# tube-connector.net
KiCad netlist of a schematic drawn in EAGLE
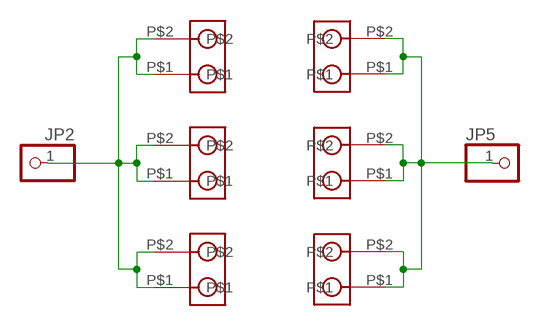
[diagram p0: schematic, sheet 1]

(export (version "E")
  (design (tool "Eeschema 10.0.6"))
  (components
    (comp (ref "JP2")
      (value "PINHD-1X1")
      (footprint "eagle-import:1X01")
      (libsource (lib "eagle-import") (part "PINHD-1X1"))
    )
    (comp (ref "JP5")
      (value "PINHD-1X1")
      (footprint "eagle-import:1X01")
      (libsource (lib "eagle-import") (part "PINHD-1X1"))
    )
    (comp (ref "U$1")
      (value "GM-CONNECTOR")
      (footprint "eagle-import:GM-CONNECTOR")
      (libsource (lib "eagle-import") (part "GM-CONNECTOR"))
    )
    (comp (ref "U$2")
      (value "GM-CONNECTOR")
      (footprint "eagle-import:GM-CONNECTOR")
      (libsource (lib "eagle-import") (part "GM-CONNECTOR"))
    )
    (comp (ref "U$3")
      (value "GM-CONNECTOR")
      (footprint "eagle-import:GM-CONNECTOR")
      (libsource (lib "eagle-import") (part "GM-CONNECTOR"))
    )
    (comp (ref "U$4")
      (value "GM-CONNECTOR")
      (footprint "eagle-import:GM-CONNECTOR")
      (libsource (lib "eagle-import") (part "GM-CONNECTOR"))
    )
    (comp (ref "U$5")
      (value "GM-CONNECTOR")
      (footprint "eagle-import:GM-CONNECTOR")
      (libsource (lib "eagle-import") (part "GM-CONNECTOR"))
    )
    (comp (ref "U$6")
      (value "GM-CONNECTOR")
      (footprint "eagle-import:GM-CONNECTOR")
      (libsource (lib "eagle-import") (part "GM-CONNECTOR"))
    )
  )
  (nets
    (net (code "1") (name "Net-(JP2-Pad1)") (class "Default")
      (node (ref "JP2") (pin "1") (pinfunction "1_1") (pintype "passive"))
      (node (ref "U$1") (pin "P$1") (pinfunction "P$1_P$1") (pintype "bidirectional"))
      (node (ref "U$1") (pin "P$2") (pinfunction "P$2_P$2") (pintype "bidirectional"))
      (node (ref "U$2") (pin "P$1") (pinfunction "P$1_P$1") (pintype "bidirectional"))
      (node (ref "U$2") (pin "P$2") (pinfunction "P$2_P$2") (pintype "bidirectional"))
      (node (ref "U$3") (pin "P$1") (pinfunction "P$1_P$1") (pintype "bidirectional"))
      (node (ref "U$3") (pin "P$2") (pinfunction "P$2_P$2") (pintype "bidirectional"))
    )
    (net (code "2") (name "Net-(JP5-Pad1)") (class "Default")
      (node (ref "JP5") (pin "1") (pinfunction "1_1") (pintype "passive"))
      (node (ref "U$4") (pin "P$1") (pinfunction "P$1_P$1") (pintype "bidirectional"))
      (node (ref "U$4") (pin "P$2") (pinfunction "P$2_P$2") (pintype "bidirectional"))
      (node (ref "U$5") (pin "P$1") (pinfunction "P$1_P$1") (pintype "bidirectional"))
      (node (ref "U$5") (pin "P$2") (pinfunction "P$2_P$2") (pintype "bidirectional"))
      (node (ref "U$6") (pin "P$1") (pinfunction "P$1_P$1") (pintype "bidirectional"))
      (node (ref "U$6") (pin "P$2") (pinfunction "P$2_P$2") (pintype "bidirectional"))
    )
  )
)
